# ESP32-Mini1-OSHPARK.net
KiCad netlist of a schematic drawn in EAGLE
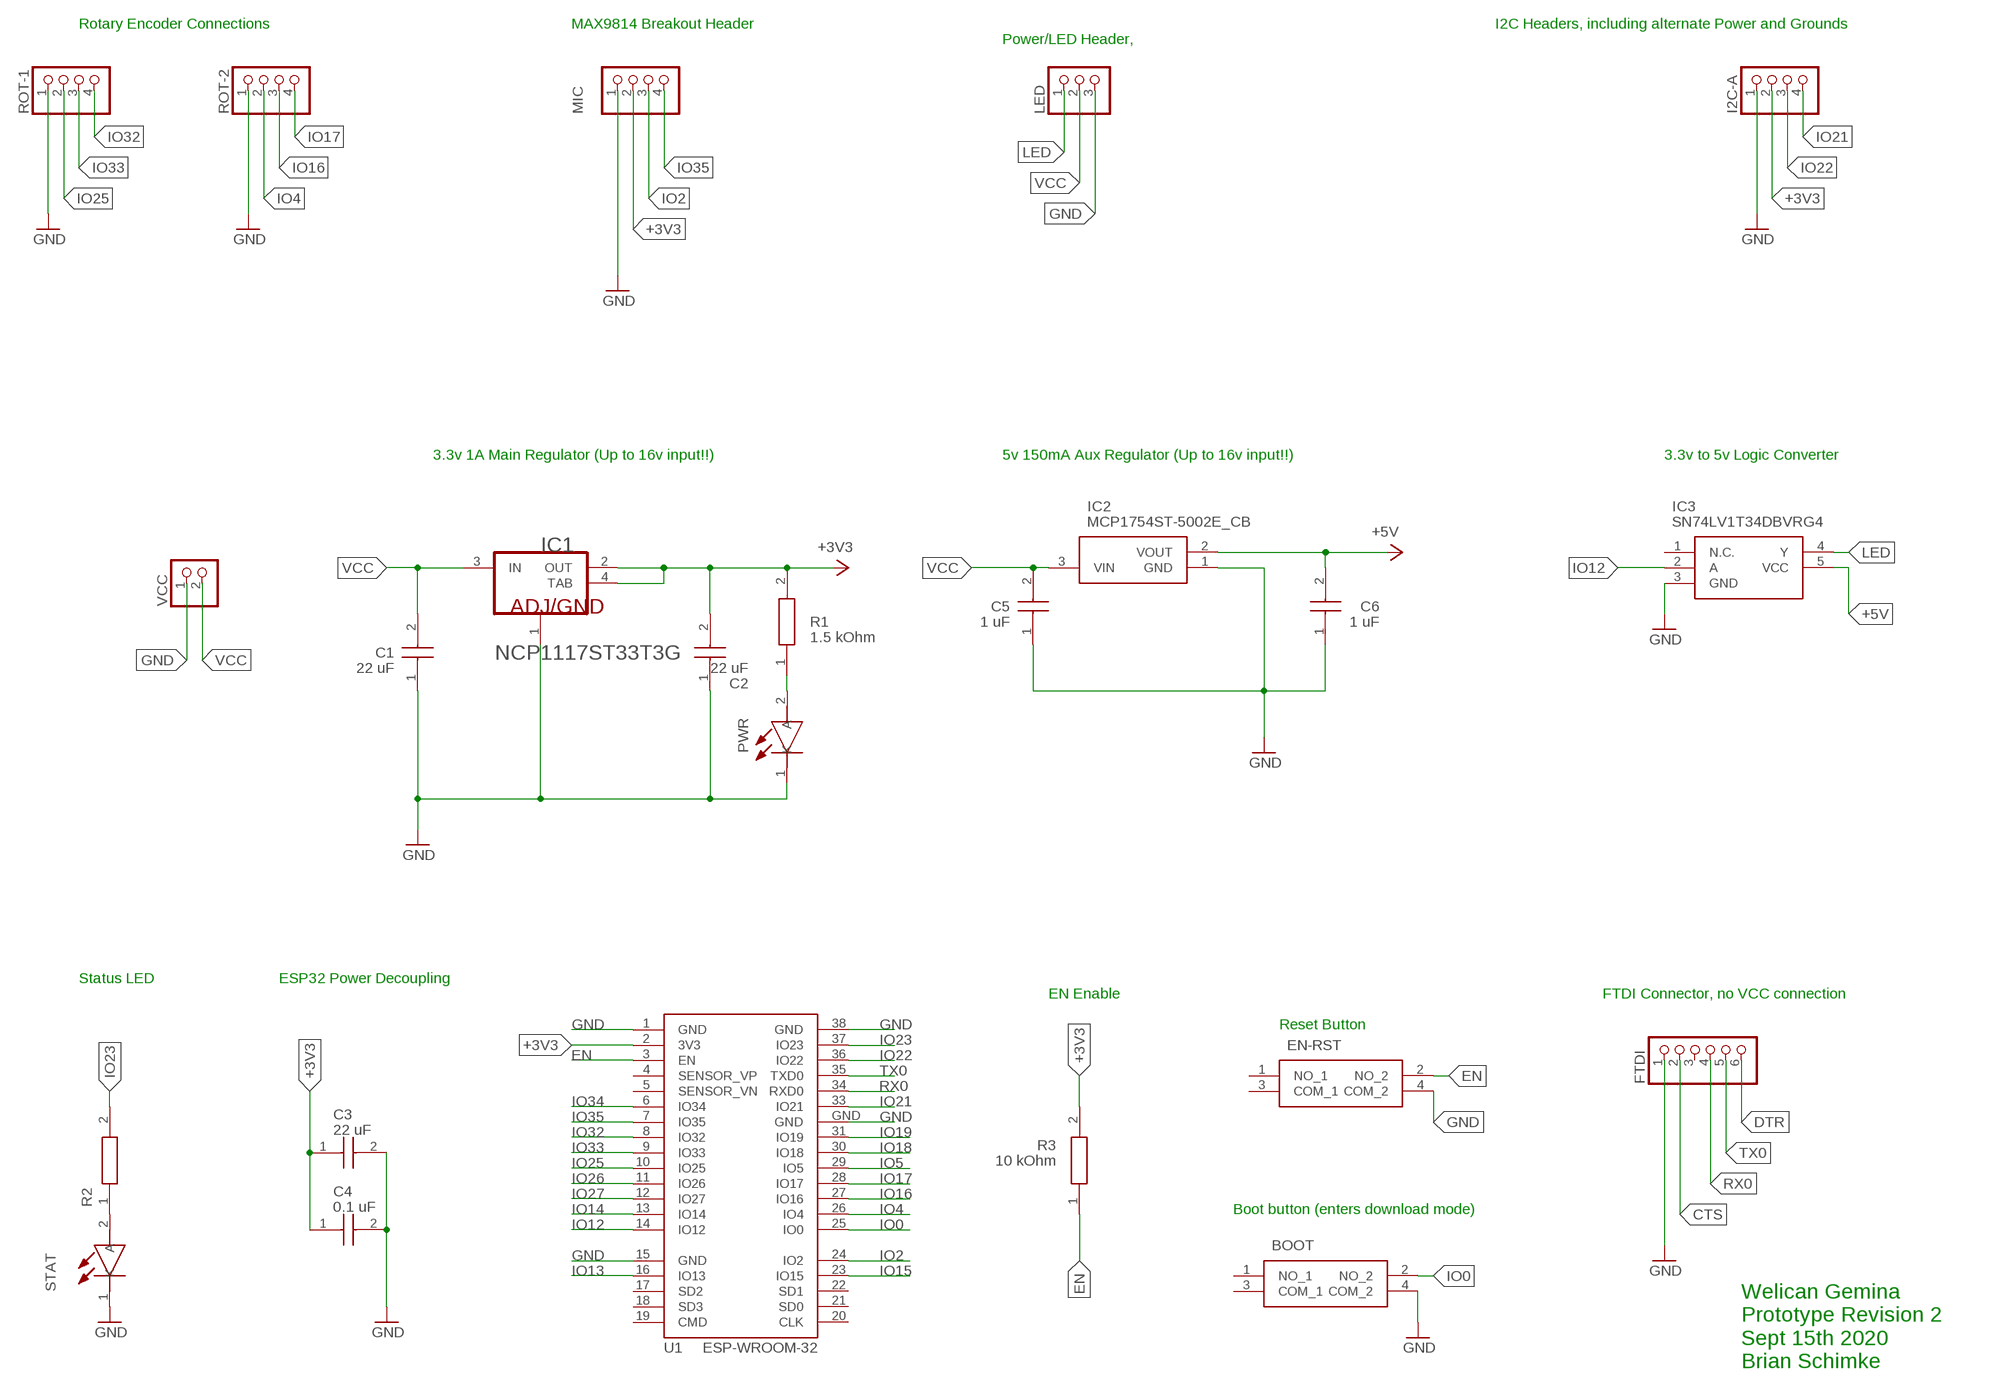
[diagram p0: schematic, sheet 1]

(export (version "E")
  (design (tool "Eeschema 10.0.6"))
  (components
    (comp (ref "BOOT")
      (value "PTS647SK70SMTR2LFS")
      (footprint "eagle-import:PTS647SK70SMTR2LFS")
      (fields (field (name "MOUSER_PART_NUMBER") "611-PTS647SK70SMTR2L"))
      (libsource (lib "eagle-import") (part "PTS647SK70SMTR2LFS"))
    )
    (comp (ref "C1")
      (value "22 uF")
      (footprint "eagle-import:CAPC3216X180N")
      (fields
        (field (name "MANUFACTURER_PART_NUMBER") "C1206C226M4PACTU")
        (field (name "MOUSER_PART_NUMBER") "80-C1206C226M4P")
      )
      (libsource (lib "eagle-import") (part "C1206C226M4PACTU"))
    )
    (comp (ref "C2")
      (value "22 uF")
      (footprint "eagle-import:CAPC3216X180N")
      (fields
        (field (name "MANUFACTURER_PART_NUMBER") "C1206C226M4PACTU")
        (field (name "MOUSER_PART_NUMBER") "80-C1206C226M4P")
      )
      (libsource (lib "eagle-import") (part "C1206C226M4PACTU"))
    )
    (comp (ref "C3")
      (value "22 uF")
      (footprint "eagle-import:CAPC3216X180N")
      (fields
        (field (name "MANUFACTURER_PART_NUMBER") "C1206C226M4PACTU")
        (field (name "MOUSER_PART_NUMBER") "80-C1206C226M4P")
      )
      (libsource (lib "eagle-import") (part "C1206C226M4PACTU"))
    )
    (comp (ref "C4")
      (value "0.1 uF")
      (footprint "eagle-import:CAPC3216X180N")
      (fields
        (field (name "MANUFACTURER_PART_NUMBER") "C1206C226M4PACTU")
        (field (name "MOUSER_PART_NUMBER") "80-C1206C226M4P")
      )
      (libsource (lib "eagle-import") (part "C1206C226M4PACTU"))
    )
    (comp (ref "C5")
      (value "1 uF")
      (footprint "eagle-import:CAPC3216X180N")
      (fields
        (field (name "MANUFACTURER_PART_NUMBER") "C1206C226M4PACTU")
        (field (name "MOUSER_PART_NUMBER") "80-C1206C226M4P")
      )
      (libsource (lib "eagle-import") (part "C1206C226M4PACTU"))
    )
    (comp (ref "C6")
      (value "1 uF")
      (footprint "eagle-import:CAPC3216X180N")
      (fields
        (field (name "MANUFACTURER_PART_NUMBER") "C1206C226M4PACTU")
        (field (name "MOUSER_PART_NUMBER") "80-C1206C226M4P")
      )
      (libsource (lib "eagle-import") (part "C1206C226M4PACTU"))
    )
    (comp (ref "EN-RST")
      (value "PTS647SK70SMTR2LFS")
      (footprint "eagle-import:PTS647SK70SMTR2LFS")
      (fields (field (name "MOUSER_PART_NUMBER") "611-PTS647SK70SMTR2L"))
      (libsource (lib "eagle-import") (part "PTS647SK70SMTR2LFS"))
    )
    (comp (ref "FTDI")
      (value "PINHD-1X6")
      (footprint "eagle-import:1X06")
      (libsource (lib "eagle-import") (part "PINHD-1X6"))
    )
    (comp (ref "I2C-A")
      (value "PINHD-1X4")
      (footprint "eagle-import:1X04")
      (libsource (lib "eagle-import") (part "PINHD-1X4"))
    )
    (comp (ref "IC1")
      (value "ON_SEMICONDUCTOR_NCP1117ST33T3GON_SEMICONDUCTOR_NCP1117ST33T3G_0_0")
      (footprint "eagle-import:ON_SEMICONDUCTOR_NCP1117ST33T3G_0")
      (fields
        (field (name "MF") "ON Semiconductor")
        (field (name "MPN") "NCP1117ST33T3G")
        (field (name "TOLERANCE") "1%")
      )
      (libsource (lib "eagle-import") (part "ON_SEMICONDUCTOR_NCP1117ST33T3GON_SEMICONDUCTOR_NCP1117ST33T3G_0_0"))
    )
    (comp (ref "IC2")
      (value "MCP1754ST-5002E_CB")
      (footprint "eagle-import:SOT95P255X145-3N")
      (fields
        (field (name "MANUFACTURER_PART_NUMBER") "MCP1754ST-5002E/CB")
        (field (name "MOUSER_PART_NUMBER") "579-MCP1754T-5002ECB")
      )
      (libsource (lib "eagle-import") (part "MCP1754ST-5002E_CB"))
    )
    (comp (ref "IC3")
      (value "SN74LV1T34DBVRG4")
      (footprint "eagle-import:SOT95P280X145-5N")
      (fields (field (name "MOUSER_PART_NUMBER") "595-SN74LV1T34DBVRG4"))
      (libsource (lib "eagle-import") (part "SN74LV1T34DBVRG4"))
    )
    (comp (ref "LED")
      (value "PINHD-1X3")
      (footprint "eagle-import:1X03")
      (libsource (lib "eagle-import") (part "PINHD-1X3"))
    )
    (comp (ref "MIC")
      (value "PINHD-1X4")
      (footprint "eagle-import:1X04")
      (libsource (lib "eagle-import") (part "PINHD-1X4"))
    )
    (comp (ref "PWR")
      (value "150120AS75000")
      (footprint "eagle-import:LEDSC320X160X78-2N")
      (fields (field (name "MOUSER_PART_NUMBER") "710-150120AS75000"))
      (libsource (lib "eagle-import") (part "150120AS75000"))
    )
    (comp (ref "R1")
      (value "1.5 kOhm")
      (footprint "eagle-import:RESC3216X60N")
      (fields
        (field (name "MANUFACTURER_PART_NUMBER") "CRCW12061K00FKEB")
        (field (name "MOUSER_PART_NUMBER") "71-CRCW12061K00FKEB")
      )
      (libsource (lib "eagle-import") (part "CRCW12061K00FKEB"))
    )
    (comp (ref "R2")
      (value "CRCW12061K00FKEB")
      (footprint "eagle-import:RESC3216X60N")
      (fields (field (name "MOUSER_PART_NUMBER") "71-CRCW12061K00FKEB"))
      (libsource (lib "eagle-import") (part "CRCW12061K00FKEB"))
    )
    (comp (ref "R3")
      (value "10 kOhm")
      (footprint "eagle-import:RESC3216X60N")
      (fields
        (field (name "MANUFACTURER_PART_NUMBER") "CRCW12061K00FKEB")
        (field (name "MOUSER_PART_NUMBER") "71-CRCW12061K00FKEB")
      )
      (libsource (lib "eagle-import") (part "CRCW12061K00FKEB"))
    )
    (comp (ref "ROT-1")
      (value "PINHD-1X4")
      (footprint "eagle-import:1X04")
      (libsource (lib "eagle-import") (part "PINHD-1X4"))
    )
    (comp (ref "ROT-2")
      (value "PINHD-1X4")
      (footprint "eagle-import:1X04")
      (libsource (lib "eagle-import") (part "PINHD-1X4"))
    )
    (comp (ref "STAT")
      (value "150120AS75000")
      (footprint "eagle-import:LEDSC320X160X78-2N")
      (fields (field (name "MOUSER_PART_NUMBER") "710-150120AS75000"))
      (libsource (lib "eagle-import") (part "150120AS75000"))
    )
    (comp (ref "U1")
      (value "ESP-WROOM-32")
      (footprint "eagle-import:ESP-WROOM-32")
      (libsource (lib "eagle-import") (part "ESP-WROOM-32"))
    )
    (comp (ref "VCC")
      (value "PINHD-1X2")
      (footprint "eagle-import:1X02")
      (libsource (lib "eagle-import") (part "PINHD-1X2"))
    )
  )
  (nets
    (net (code "1") (name "+3V3") (class "Default")
      (node (ref "C2") (pin "2") (pinfunction "2_2") (pintype "bidirectional"))
      (node (ref "C3") (pin "1") (pinfunction "1_1") (pintype "bidirectional"))
      (node (ref "C4") (pin "1") (pinfunction "1_1") (pintype "bidirectional"))
      (node (ref "I2C-A") (pin "2") (pinfunction "2_2") (pintype "passive"))
      (node (ref "IC1") (pin "2") (pinfunction "OUT_2") (pintype "power_in"))
      (node (ref "IC1") (pin "4") (pinfunction "TAB_4") (pintype "passive"))
      (node (ref "MIC") (pin "2") (pinfunction "2_2") (pintype "passive"))
      (node (ref "R1") (pin "2") (pinfunction "2_2") (pintype "bidirectional"))
      (node (ref "R3") (pin "2") (pinfunction "2_2") (pintype "bidirectional"))
      (node (ref "U1") (pin "2") (pinfunction "3V3_2") (pintype "power_in"))
    )
    (net (code "2") (name "+5V") (class "Default")
      (node (ref "C6") (pin "2") (pinfunction "2_2") (pintype "bidirectional"))
      (node (ref "IC2") (pin "2") (pinfunction "VOUT_2") (pintype "bidirectional"))
      (node (ref "IC3") (pin "5") (pinfunction "VCC_5") (pintype "bidirectional"))
    )
    (net (code "3") (name "/IO5") (class "Default")
      (node (ref "U1") (pin "29") (pinfunction "IO5_29") (pintype "bidirectional"))
    )
    (net (code "4") (name "/IO13") (class "Default")
      (node (ref "U1") (pin "16") (pinfunction "IO13_16") (pintype "bidirectional"))
    )
    (net (code "5") (name "/IO14") (class "Default")
      (node (ref "U1") (pin "13") (pinfunction "IO14_13") (pintype "bidirectional"))
    )
    (net (code "6") (name "/IO15") (class "Default")
      (node (ref "U1") (pin "23") (pinfunction "IO15_23") (pintype "bidirectional"))
    )
    (net (code "7") (name "/IO18") (class "Default")
      (node (ref "U1") (pin "30") (pinfunction "IO18_30") (pintype "bidirectional"))
    )
    (net (code "8") (name "/IO19") (class "Default")
      (node (ref "U1") (pin "31") (pinfunction "IO19_31") (pintype "bidirectional"))
    )
    (net (code "9") (name "/IO26") (class "Default")
      (node (ref "U1") (pin "11") (pinfunction "IO26_11") (pintype "bidirectional"))
    )
    (net (code "10") (name "/IO27") (class "Default")
      (node (ref "U1") (pin "12") (pinfunction "IO27_12") (pintype "bidirectional"))
    )
    (net (code "11") (name "/IO34") (class "Default")
      (node (ref "U1") (pin "6") (pinfunction "IO34_6") (pintype "bidirectional"))
    )
    (net (code "12") (name "CTS") (class "Default")
      (node (ref "FTDI") (pin "2") (pinfunction "2_2") (pintype "passive"))
    )
    (net (code "13") (name "DTR") (class "Default")
      (node (ref "FTDI") (pin "6") (pinfunction "6_6") (pintype "passive"))
    )
    (net (code "14") (name "EN") (class "Default")
      (node (ref "EN-RST") (pin "2") (pinfunction "NO_2_2") (pintype "bidirectional"))
      (node (ref "R3") (pin "1") (pinfunction "1_1") (pintype "bidirectional"))
      (node (ref "U1") (pin "3") (pinfunction "EN_3") (pintype "input"))
    )
    (net (code "15") (name "GND") (class "Default")
      (node (ref "BOOT") (pin "4") (pinfunction "COM_2_4") (pintype "bidirectional"))
      (node (ref "C1") (pin "1") (pinfunction "1_1") (pintype "bidirectional"))
      (node (ref "C2") (pin "1") (pinfunction "1_1") (pintype "bidirectional"))
      (node (ref "C3") (pin "2") (pinfunction "2_2") (pintype "bidirectional"))
      (node (ref "C4") (pin "2") (pinfunction "2_2") (pintype "bidirectional"))
      (node (ref "C5") (pin "1") (pinfunction "1_1") (pintype "bidirectional"))
      (node (ref "C6") (pin "1") (pinfunction "1_1") (pintype "bidirectional"))
      (node (ref "EN-RST") (pin "4") (pinfunction "COM_2_4") (pintype "bidirectional"))
      (node (ref "FTDI") (pin "1") (pinfunction "1_1") (pintype "passive"))
      (node (ref "I2C-A") (pin "1") (pinfunction "1_1") (pintype "passive"))
      (node (ref "IC1") (pin "1") (pinfunction "ADJ/GND_1") (pintype "passive"))
      (node (ref "IC2") (pin "1") (pinfunction "GND_1") (pintype "bidirectional"))
      (node (ref "IC3") (pin "3") (pinfunction "GND_3") (pintype "bidirectional"))
      (node (ref "LED") (pin "3") (pinfunction "3_3") (pintype "passive"))
      (node (ref "MIC") (pin "1") (pinfunction "1_1") (pintype "passive"))
      (node (ref "PWR") (pin "1") (pinfunction "K_1") (pintype "bidirectional"))
      (node (ref "ROT-1") (pin "1") (pinfunction "1_1") (pintype "passive"))
      (node (ref "ROT-2") (pin "1") (pinfunction "1_1") (pintype "passive"))
      (node (ref "STAT") (pin "1") (pinfunction "K_1") (pintype "bidirectional"))
      (node (ref "U1") (pin "1") (pinfunction "GND_1") (pintype "power_in"))
      (node (ref "U1") (pin "15") (pinfunction "GND_15") (pintype "power_in"))
      (node (ref "U1") (pin "38") (pinfunction "GND_38") (pintype "power_in"))
      (node (ref "U1") (pin "GND") (pinfunction "GND_GND") (pintype "power_in"))
      (node (ref "VCC") (pin "1") (pinfunction "1_1") (pintype "passive"))
    )
    (net (code "16") (name "IO0") (class "Default")
      (node (ref "BOOT") (pin "2") (pinfunction "NO_2_2") (pintype "bidirectional"))
      (node (ref "U1") (pin "25") (pinfunction "IO0_25") (pintype "bidirectional"))
    )
    (net (code "17") (name "IO2") (class "Default")
      (node (ref "MIC") (pin "3") (pinfunction "3_3") (pintype "passive"))
      (node (ref "U1") (pin "24") (pinfunction "IO2_24") (pintype "bidirectional"))
    )
    (net (code "18") (name "IO4") (class "Default")
      (node (ref "ROT-2") (pin "2") (pinfunction "2_2") (pintype "passive"))
      (node (ref "U1") (pin "26") (pinfunction "IO4_26") (pintype "bidirectional"))
    )
    (net (code "19") (name "IO12") (class "Default")
      (node (ref "IC3") (pin "2") (pinfunction "A_2") (pintype "bidirectional"))
      (node (ref "U1") (pin "14") (pinfunction "IO12_14") (pintype "bidirectional"))
    )
    (net (code "20") (name "IO16") (class "Default")
      (node (ref "ROT-2") (pin "3") (pinfunction "3_3") (pintype "passive"))
      (node (ref "U1") (pin "27") (pinfunction "IO16_27") (pintype "bidirectional"))
    )
    (net (code "21") (name "IO17") (class "Default")
      (node (ref "ROT-2") (pin "4") (pinfunction "4_4") (pintype "passive"))
      (node (ref "U1") (pin "28") (pinfunction "IO17_28") (pintype "bidirectional"))
    )
    (net (code "22") (name "IO21") (class "Default")
      (node (ref "I2C-A") (pin "4") (pinfunction "4_4") (pintype "passive"))
      (node (ref "U1") (pin "33") (pinfunction "IO21_33") (pintype "bidirectional"))
    )
    (net (code "23") (name "IO22") (class "Default")
      (node (ref "I2C-A") (pin "3") (pinfunction "3_3") (pintype "passive"))
      (node (ref "U1") (pin "36") (pinfunction "IO22_36") (pintype "bidirectional"))
    )
    (net (code "24") (name "IO23") (class "Default")
      (node (ref "R2") (pin "2") (pinfunction "2_2") (pintype "bidirectional"))
      (node (ref "U1") (pin "37") (pinfunction "IO23_37") (pintype "bidirectional"))
    )
    (net (code "25") (name "IO25") (class "Default")
      (node (ref "ROT-1") (pin "2") (pinfunction "2_2") (pintype "passive"))
      (node (ref "U1") (pin "10") (pinfunction "IO25_10") (pintype "bidirectional"))
    )
    (net (code "26") (name "IO32") (class "Default")
      (node (ref "ROT-1") (pin "4") (pinfunction "4_4") (pintype "passive"))
      (node (ref "U1") (pin "8") (pinfunction "IO32_8") (pintype "bidirectional"))
    )
    (net (code "27") (name "IO33") (class "Default")
      (node (ref "ROT-1") (pin "3") (pinfunction "3_3") (pintype "passive"))
      (node (ref "U1") (pin "9") (pinfunction "IO33_9") (pintype "bidirectional"))
    )
    (net (code "28") (name "IO35") (class "Default")
      (node (ref "MIC") (pin "4") (pinfunction "4_4") (pintype "passive"))
      (node (ref "U1") (pin "7") (pinfunction "IO35_7") (pintype "bidirectional"))
    )
    (net (code "29") (name "LED") (class "Default")
      (node (ref "IC3") (pin "4") (pinfunction "Y_4") (pintype "bidirectional"))
      (node (ref "LED") (pin "1") (pinfunction "1_1") (pintype "passive"))
    )
    (net (code "30") (name "Net-(PWR-A)") (class "Default")
      (node (ref "PWR") (pin "2") (pinfunction "A_2") (pintype "bidirectional"))
      (node (ref "R1") (pin "1") (pinfunction "1_1") (pintype "bidirectional"))
    )
    (net (code "31") (name "Net-(STAT-A)") (class "Default")
      (node (ref "R2") (pin "1") (pinfunction "1_1") (pintype "bidirectional"))
      (node (ref "STAT") (pin "2") (pinfunction "A_2") (pintype "bidirectional"))
    )
    (net (code "32") (name "RX0") (class "Default")
      (node (ref "FTDI") (pin "4") (pinfunction "4_4") (pintype "passive"))
      (node (ref "U1") (pin "34") (pinfunction "RXD0_34") (pintype "bidirectional"))
    )
    (net (code "33") (name "TX0") (class "Default")
      (node (ref "FTDI") (pin "5") (pinfunction "5_5") (pintype "passive"))
      (node (ref "U1") (pin "35") (pinfunction "TXD0_35") (pintype "bidirectional"))
    )
    (net (code "34") (name "VCC") (class "Default")
      (node (ref "C1") (pin "2") (pinfunction "2_2") (pintype "bidirectional"))
      (node (ref "C5") (pin "2") (pinfunction "2_2") (pintype "bidirectional"))
      (node (ref "IC1") (pin "3") (pinfunction "IN_3") (pintype "power_in"))
      (node (ref "IC2") (pin "3") (pinfunction "VIN_3") (pintype "bidirectional"))
      (node (ref "LED") (pin "2") (pinfunction "2_2") (pintype "passive"))
      (node (ref "VCC") (pin "2") (pinfunction "2_2") (pintype "passive"))
    )
    (net (code "35") (name "unconnected-(BOOT-COM_1-Pad3)") (class "Default")
      (node (ref "BOOT") (pin "3") (pinfunction "COM_1_3") (pintype "bidirectional"))
    )
    (net (code "36") (name "unconnected-(BOOT-NO_1-Pad1)") (class "Default")
      (node (ref "BOOT") (pin "1") (pinfunction "NO_1_1") (pintype "bidirectional"))
    )
    (net (code "37") (name "unconnected-(EN-RST-COM_1-Pad3)") (class "Default")
      (node (ref "EN-RST") (pin "3") (pinfunction "COM_1_3") (pintype "bidirectional"))
    )
    (net (code "38") (name "unconnected-(EN-RST-NO_1-Pad1)") (class "Default")
      (node (ref "EN-RST") (pin "1") (pinfunction "NO_1_1") (pintype "bidirectional"))
    )
    (net (code "39") (name "unconnected-(FTDI-Pad3)") (class "Default")
      (node (ref "FTDI") (pin "3") (pinfunction "3_3") (pintype "passive"))
    )
    (net (code "40") (name "unconnected-(IC3-N.C.-Pad1)") (class "Default")
      (node (ref "IC3") (pin "1") (pinfunction "N.C._1") (pintype "no_connect"))
    )
    (net (code "41") (name "unconnected-(U1-CLK-Pad20)") (class "Default")
      (node (ref "U1") (pin "20") (pinfunction "CLK_20") (pintype "bidirectional"))
    )
    (net (code "42") (name "unconnected-(U1-CMD-Pad19)") (class "Default")
      (node (ref "U1") (pin "19") (pinfunction "CMD_19") (pintype "bidirectional"))
    )
    (net (code "43") (name "unconnected-(U1-SD0-Pad21)") (class "Default")
      (node (ref "U1") (pin "21") (pinfunction "SD0_21") (pintype "bidirectional"))
    )
    (net (code "44") (name "unconnected-(U1-SD1-Pad22)") (class "Default")
      (node (ref "U1") (pin "22") (pinfunction "SD1_22") (pintype "bidirectional"))
    )
    (net (code "45") (name "unconnected-(U1-SD2-Pad17)") (class "Default")
      (node (ref "U1") (pin "17") (pinfunction "SD2_17") (pintype "bidirectional"))
    )
    (net (code "46") (name "unconnected-(U1-SD3-Pad18)") (class "Default")
      (node (ref "U1") (pin "18") (pinfunction "SD3_18") (pintype "bidirectional"))
    )
    (net (code "47") (name "unconnected-(U1-SENSOR_VN-Pad5)") (class "Default")
      (node (ref "U1") (pin "5") (pinfunction "SENSOR_VN_5") (pintype "bidirectional"))
    )
    (net (code "48") (name "unconnected-(U1-SENSOR_VP-Pad4)") (class "Default")
      (node (ref "U1") (pin "4") (pinfunction "SENSOR_VP_4") (pintype "bidirectional"))
    )
  )
)
